# LM386_basic.net
KiCad netlist of a schematic drawn in EAGLE
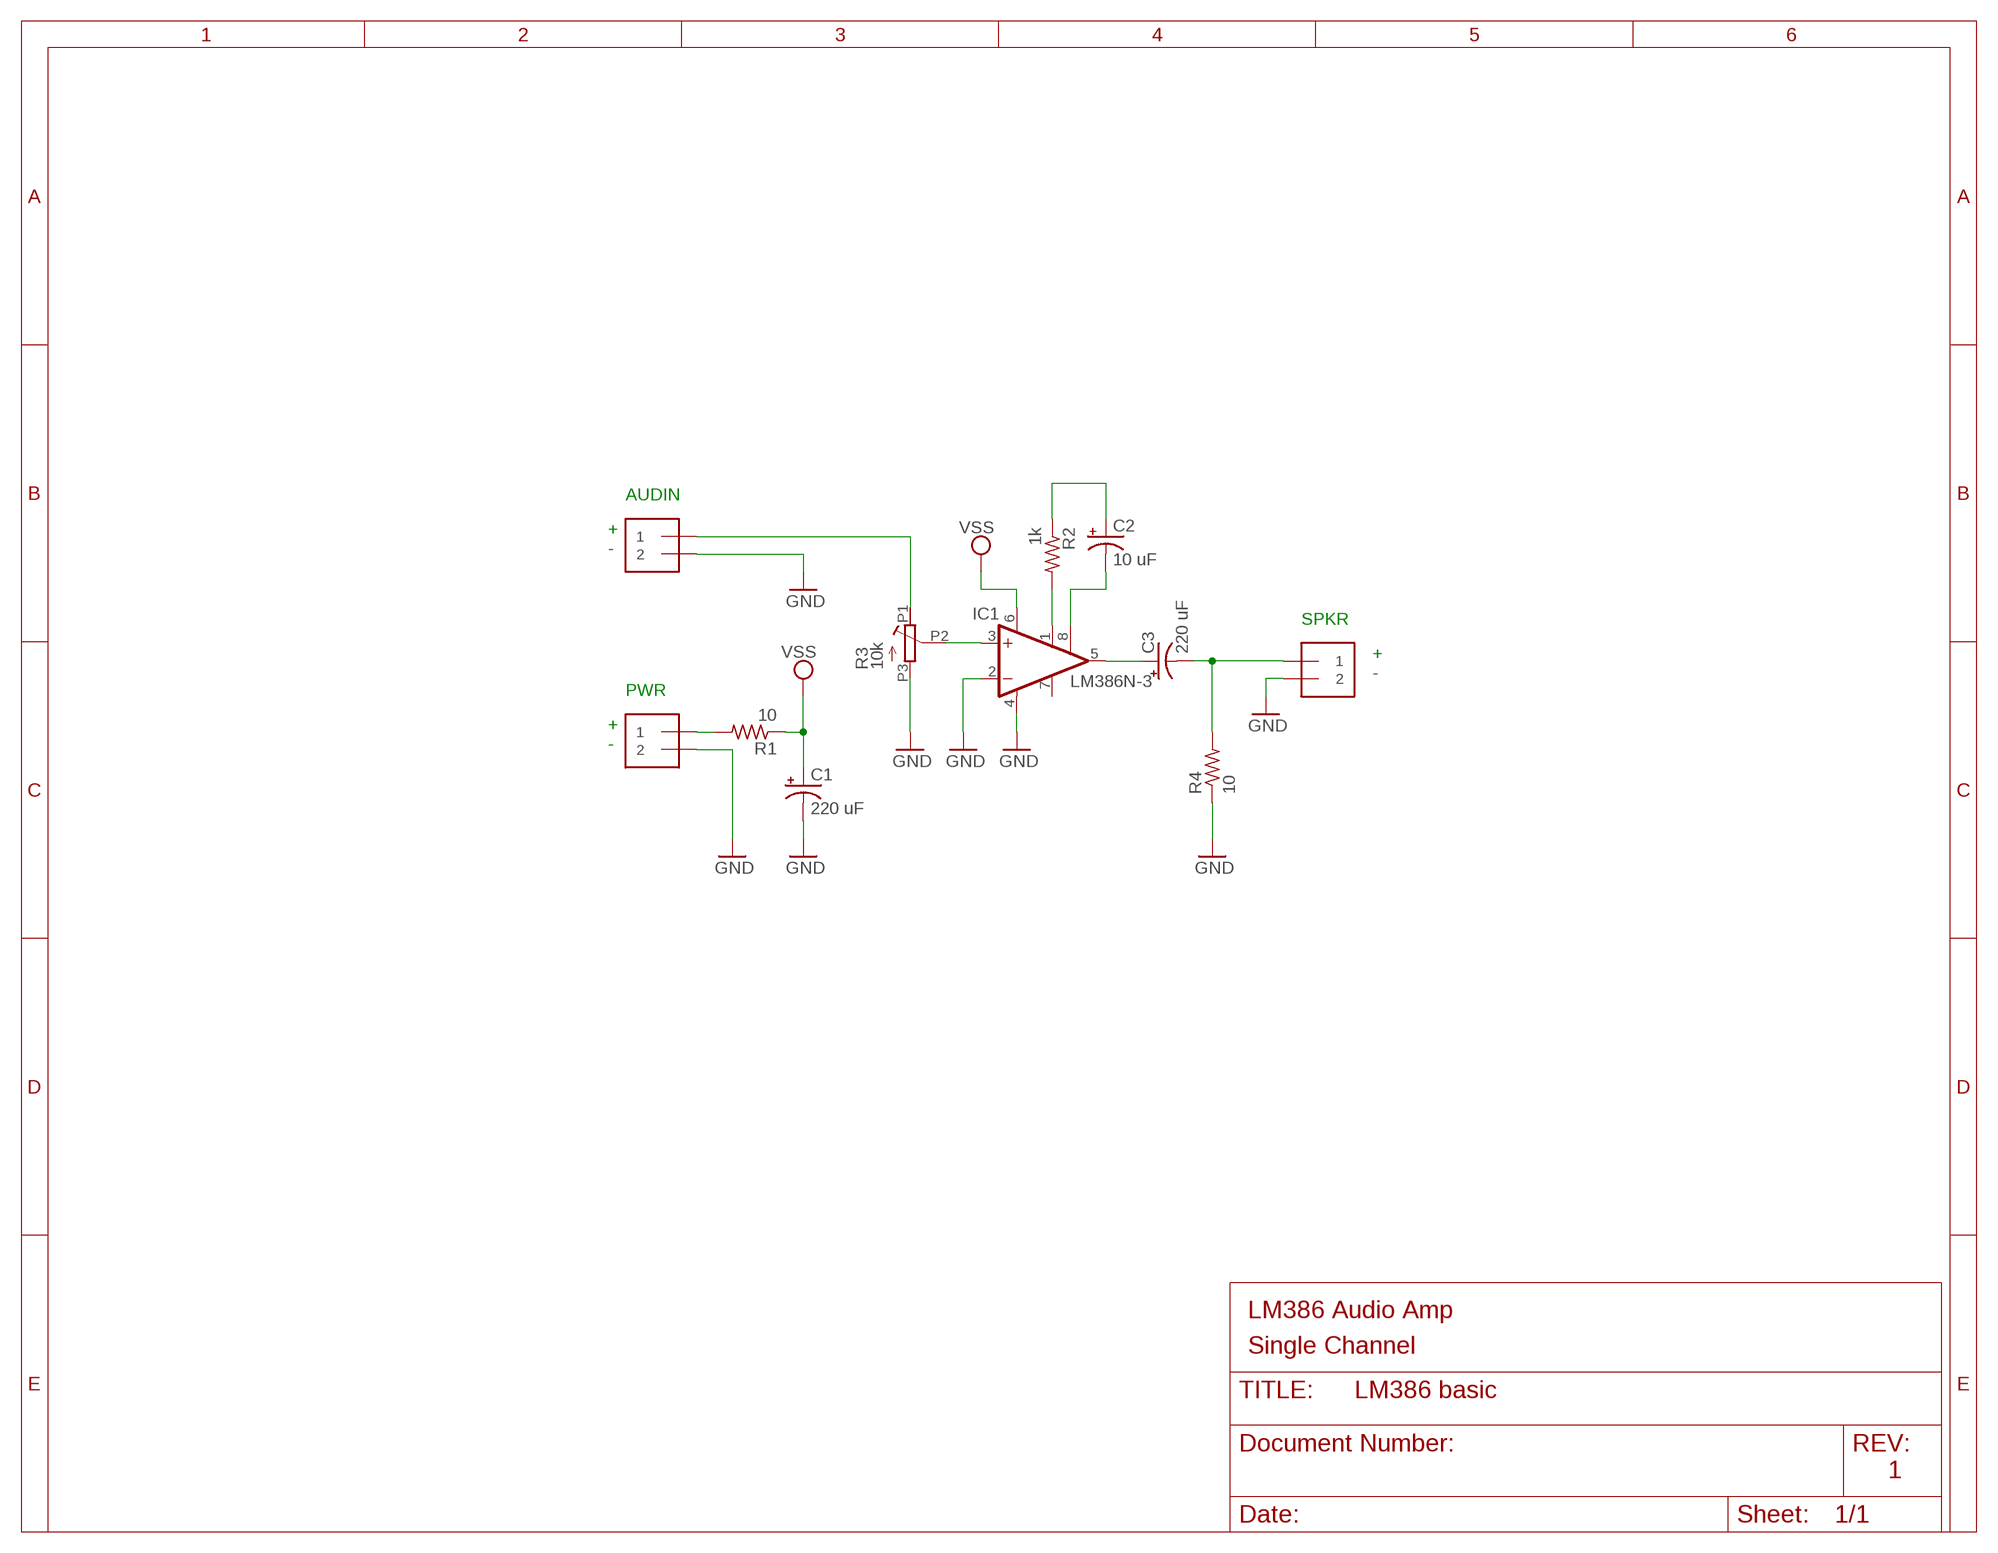
[diagram p0: schematic, sheet 1]

(export (version "E")
  (design (tool "Eeschema 10.0.6"))
  (components
    (comp (ref "AUDIN")
      (value "1X2-3.5MM")
      (footprint "eagle-import:1X2-3.5MM")
      (libsource (lib "eagle-import") (part "1X2-3.5MM"))
    )
    (comp (ref "C1")
      (value "220 uF")
      (footprint "eagle-import:E2,5-6")
      (libsource (lib "eagle-import") (part "CPOL-USE2.5-6"))
    )
    (comp (ref "C2")
      (value "10 uF")
      (footprint "eagle-import:E2-5")
      (libsource (lib "eagle-import") (part "rcl_CPOL-USE2-5"))
    )
    (comp (ref "C3")
      (value "220 uF")
      (footprint "eagle-import:E2,5-6")
      (libsource (lib "eagle-import") (part "CPOL-USE2.5-6"))
    )
    (comp (ref "IC1")
      (value "LM386N-3")
      (footprint "eagle-import:DIL08")
      (libsource (lib "eagle-import") (part "LM386?-N3"))
    )
    (comp (ref "PWR")
      (value "1X2-3.5MM")
      (footprint "eagle-import:1X2-3.5MM")
      (libsource (lib "eagle-import") (part "1X2-3.5MM"))
    )
    (comp (ref "R1")
      (value "10")
      (footprint "eagle-import:0309_12")
      (libsource (lib "eagle-import") (part "R-US_0309/12"))
    )
    (comp (ref "R2")
      (value "1k")
      (footprint "eagle-import:0309_12")
      (libsource (lib "eagle-import") (part "R-US_0309/12"))
    )
    (comp (ref "R3")
      (value "10k")
      (footprint "eagle-import:POT-THRU-01")
      (libsource (lib "eagle-import") (part "TRIMPOT"))
    )
    (comp (ref "R4")
      (value "10")
      (footprint "eagle-import:0309_12")
      (libsource (lib "eagle-import") (part "R-US_0309/12"))
    )
    (comp (ref "SPKR")
      (value "1X2-3.5MM")
      (footprint "eagle-import:1X2-3.5MM")
      (libsource (lib "eagle-import") (part "1X2-3.5MM"))
    )
  )
  (nets
    (net (code "1") (name "GND") (class "Default")
      (node (ref "AUDIN") (pin "2") (pinfunction "2_2") (pintype "passive"))
      (node (ref "C1") (pin "-") (pinfunction "-_-") (pintype "passive"))
      (node (ref "IC1") (pin "2") (pinfunction "-IN_2") (pintype "input"))
      (node (ref "IC1") (pin "4") (pinfunction "GND_4") (pintype "power_in"))
      (node (ref "PWR") (pin "2") (pinfunction "2_2") (pintype "passive"))
      (node (ref "R3") (pin "P3") (pinfunction "A_P3") (pintype "passive"))
      (node (ref "R4") (pin "1") (pinfunction "1_1") (pintype "passive"))
      (node (ref "SPKR") (pin "2") (pinfunction "2_2") (pintype "passive"))
    )
    (net (code "2") (name "Net-(C2-Pad+)") (class "Default")
      (node (ref "C2") (pin "+") (pinfunction "+_+") (pintype "passive"))
      (node (ref "R2") (pin "1") (pinfunction "1_1") (pintype "passive"))
    )
    (net (code "3") (name "Net-(C2-Pad-)") (class "Default")
      (node (ref "C2") (pin "-") (pinfunction "-_-") (pintype "passive"))
      (node (ref "IC1") (pin "8") (pinfunction "GAIN_8") (pintype "passive"))
    )
    (net (code "4") (name "Net-(C3-Pad-)") (class "Default")
      (node (ref "C3") (pin "-") (pinfunction "-_-") (pintype "passive"))
      (node (ref "R4") (pin "2") (pinfunction "2_2") (pintype "passive"))
      (node (ref "SPKR") (pin "1") (pinfunction "1_1") (pintype "passive"))
    )
    (net (code "5") (name "Net-(IC1-+IN)") (class "Default")
      (node (ref "IC1") (pin "3") (pinfunction "+IN_3") (pintype "input"))
      (node (ref "R3") (pin "P2") (pinfunction "S_P2") (pintype "passive"))
    )
    (net (code "6") (name "Net-(IC1-GAIN-Pad1)") (class "Default")
      (node (ref "IC1") (pin "1") (pinfunction "GAIN_1") (pintype "passive"))
      (node (ref "R2") (pin "2") (pinfunction "2_2") (pintype "passive"))
    )
    (net (code "7") (name "Net-(IC1-OUT)") (class "Default")
      (node (ref "C3") (pin "+") (pinfunction "+_+") (pintype "passive"))
      (node (ref "IC1") (pin "5") (pinfunction "OUT_5") (pintype "output"))
    )
    (net (code "8") (name "Net-(PWR-Pad1)") (class "Default")
      (node (ref "PWR") (pin "1") (pinfunction "1_1") (pintype "passive"))
      (node (ref "R1") (pin "2") (pinfunction "2_2") (pintype "passive"))
    )
    (net (code "9") (name "Net-(R3-E)") (class "Default")
      (node (ref "AUDIN") (pin "1") (pinfunction "1_1") (pintype "passive"))
      (node (ref "R3") (pin "P1") (pinfunction "E_P1") (pintype "passive"))
    )
    (net (code "10") (name "VSS") (class "Default")
      (node (ref "C1") (pin "+") (pinfunction "+_+") (pintype "passive"))
      (node (ref "IC1") (pin "6") (pinfunction "VS_6") (pintype "power_in"))
      (node (ref "R1") (pin "1") (pinfunction "1_1") (pintype "passive"))
    )
    (net (code "11") (name "unconnected-(IC1-BYPASS-Pad7)") (class "Default")
      (node (ref "IC1") (pin "7") (pinfunction "BYPASS_7") (pintype "passive"))
    )
  )
)
